# power_cpu.net
KiCad netlist of a schematic drawn in Altium Designer
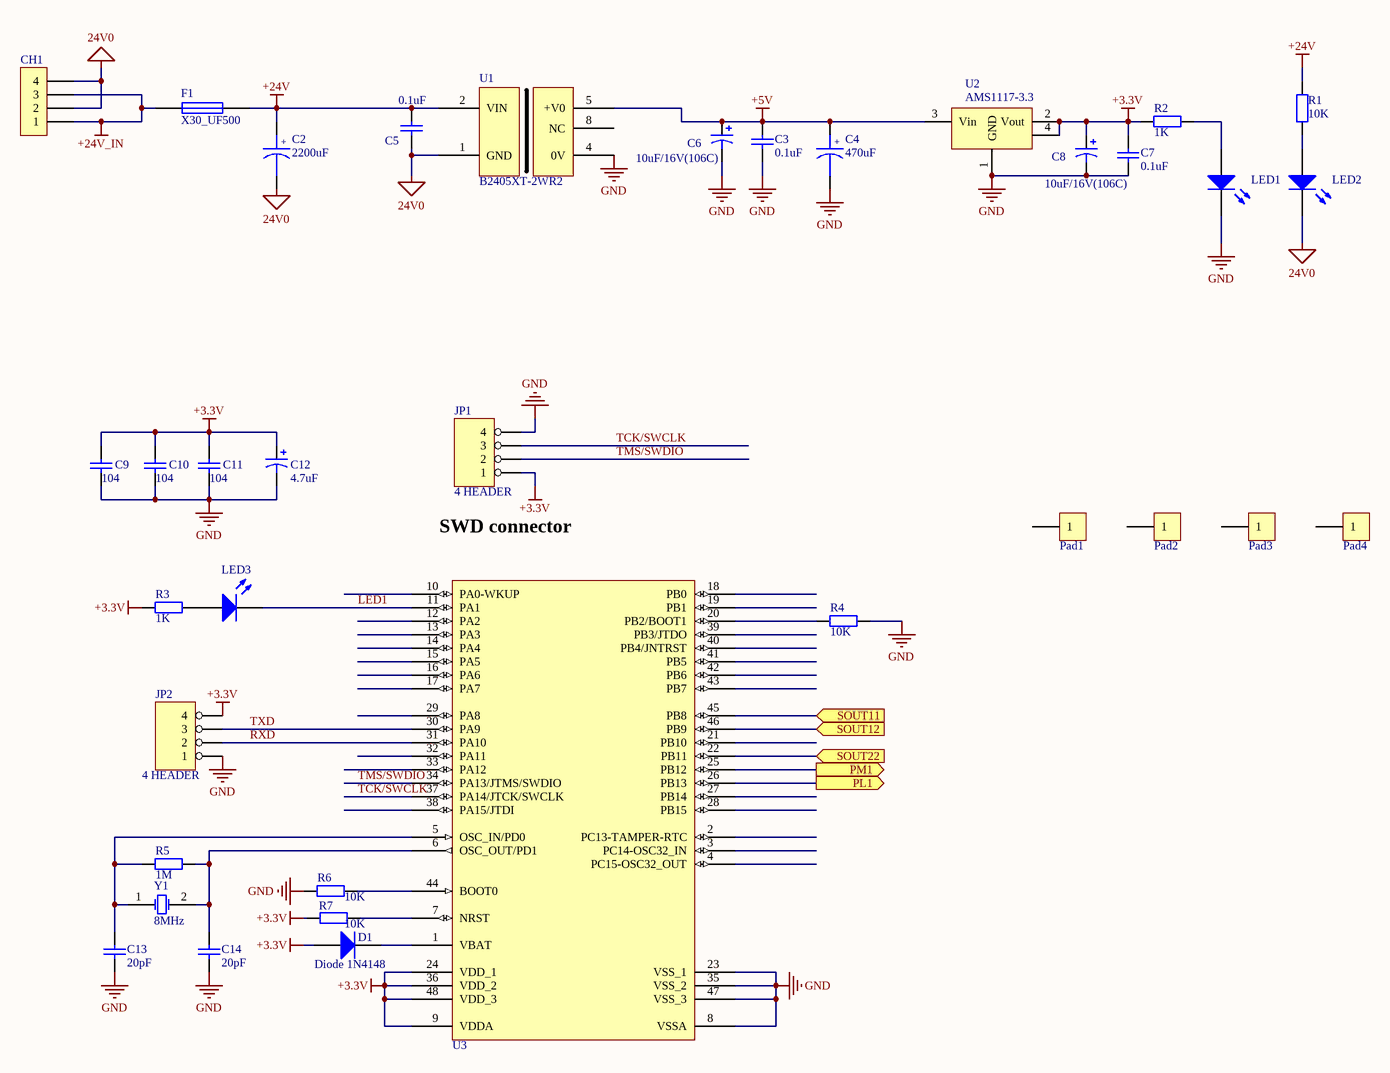
[diagram p0: power_cpu.SchDoc]

(export (version "E")
  (design (tool "Eeschema 10.0.6"))
  (components
    (comp (ref "C2")
      (value "C_2200uF")
      (footprint "C7.8*17")
      (fields (field (name "ALTIUM_UNNAMED_1") "2200uF"))
      (libsource (lib "myIntegrated_Library1") (part "C_2200uF"))
    )
    (comp (ref "C3")
      (value "0.1uF")
      (footprint "0805")
      (description "Capacitor")
      (fields (field (name "Comment") "Cap") (field (name "PUBLISHER") "Altium Limited"))
      (libsource (lib "Miscellaneous Devices") (part "Cap"))
    )
    (comp (ref "C4")
      (value "C_2200uF")
      (footprint "C5*10")
      (fields (field (name "ALTIUM_UNNAMED_1") "470uF"))
      (libsource (lib "myIntegrated_Library1") (part "C_2200uF"))
    )
    (comp (ref "C5")
      (value "0.1uF")
      (footprint "0805")
      (description "Capacitor")
      (fields (field (name "Comment") "Cap") (field (name "PUBLISHER") "Altium Limited"))
      (libsource (lib "Miscellaneous Devices") (part "Cap"))
    )
    (comp (ref "C6")
      (value "10uF/16V(106C)")
      (footprint "CAP A-3216")
      (description "Polarized Capacitor (Surface Mount)")
      (fields (field (name "Comment") "Cap Pol3") (field (name "PUBLISHER") "Altium Limited"))
      (libsource (lib "Miscellaneous Devices") (part "Cap Pol3"))
    )
    (comp (ref "C7")
      (value "0.1uF")
      (footprint "0805")
      (description "Capacitor")
      (fields (field (name "Comment") "Cap") (field (name "PUBLISHER") "Altium Limited"))
      (libsource (lib "Miscellaneous Devices") (part "Cap"))
    )
    (comp (ref "C8")
      (value "10uF/16V(106C)")
      (footprint "CAP A-3216")
      (description "Polarized Capacitor (Surface Mount)")
      (fields (field (name "Comment") "Cap Pol3") (field (name "PUBLISHER") "Altium Limited"))
      (libsource (lib "Miscellaneous Devices") (part "Cap Pol3"))
    )
    (comp (ref "C9")
      (value "104")
      (footprint "0805")
      (description "Capacitor")
      (fields (field (name "Comment") "Cap") (field (name "PUBLISHER") "Altium Limited"))
      (libsource (lib "Miscellaneous Devices") (part "Cap"))
    )
    (comp (ref "C10")
      (value "104")
      (footprint "0805")
      (description "Capacitor")
      (fields (field (name "Comment") "Cap") (field (name "PUBLISHER") "Altium Limited"))
      (libsource (lib "Miscellaneous Devices") (part "Cap"))
    )
    (comp (ref "C11")
      (value "104")
      (footprint "0805")
      (description "Capacitor")
      (fields (field (name "Comment") "Cap") (field (name "PUBLISHER") "Altium Limited"))
      (libsource (lib "Miscellaneous Devices") (part "Cap"))
    )
    (comp (ref "C12")
      (value "4.7uF")
      (footprint "3225[1210]")
      (description "Polarized Capacitor (Radial)")
      (fields (field (name "Comment") "Cap Pol1") (field (name "PUBLISHER") "Altium Limited"))
      (libsource (lib "Miscellaneous Devices") (part "Cap Pol1"))
    )
    (comp (ref "C13")
      (value "20pF")
      (footprint "0805")
      (description "Capacitor")
      (fields (field (name "Comment") "Cap") (field (name "PUBLISHER") "Altium Limited"))
      (libsource (lib "开发板元件库") (part "Cap"))
    )
    (comp (ref "C14")
      (value "20pF")
      (footprint "0805")
      (description "Capacitor")
      (fields (field (name "Comment") "Cap") (field (name "PUBLISHER") "Altium Limited"))
      (libsource (lib "开发板元件库") (part "Cap"))
    )
    (comp (ref "CH1")
      (value "HEADER1X4")
      (footprint "CH3.96-4PIN")
      (libsource (lib "myIntegrated_Library1") (part "HEADER1X4"))
    )
    (comp (ref "D1")
      (value "Diode 1N4148")
      (footprint "LL34")
      (description "High Conductance Fast Diode")
      (fields (field (name "PUBLISHER") "Altium Limited"))
      (libsource (lib "Miscellaneous Devices") (part "Diode 1N4148"))
    )
    (comp (ref "F1")
      (value "X30_UF500")
      (footprint "X30UF600")
      (description "Fuse")
      (fields (field (name "PUBLISHER") "Altium Limited"))
      (libsource (lib "Miscellaneous Devices") (part "Fuse 1"))
    )
    (comp (ref "JP1")
      (value "4 HEADER")
      (footprint "CON4_1.5")
      (description "4 Pin Header")
      (libsource (lib "Miscellaneous Devices") (part "4 HEADER"))
    )
    (comp (ref "JP2")
      (value "4 HEADER")
      (footprint "HDR1X4")
      (description "4 Pin Header")
      (libsource (lib "myIntegrated_Library1") (part "4 HEADER"))
    )
    (comp (ref "LED1")
      (value "~")
      (footprint "LED-0805")
      (description "Typical RED, GREEN, YELLOW, AMBER GaAs LED")
      (fields (field (name "PUBLISHER") "Altium Limited"))
      (libsource (lib "Miscellaneous Devices") (part "LED2"))
    )
    (comp (ref "LED2")
      (value "~")
      (footprint "LED-0805")
      (description "Typical RED, GREEN, YELLOW, AMBER GaAs LED")
      (fields (field (name "PUBLISHER") "Altium Limited"))
      (libsource (lib "Miscellaneous Devices") (part "LED2"))
    )
    (comp (ref "LED3")
      (value "~")
      (footprint "LED-0805")
      (description "Typical RED, GREEN, YELLOW, AMBER GaAs LED")
      (fields (field (name "PUBLISHER") "Altium Limited"))
      (libsource (lib "Miscellaneous Devices") (part "LED2"))
    )
    (comp (ref "Pad1")
      (value "Pad")
      (footprint "pad35")
      (libsource (lib "myIntegrated_Library1") (part "Pad"))
    )
    (comp (ref "Pad2")
      (value "Pad")
      (footprint "pad35")
      (libsource (lib "myIntegrated_Library1") (part "Pad"))
    )
    (comp (ref "Pad3")
      (value "Pad")
      (footprint "pad35")
      (libsource (lib "myIntegrated_Library1") (part "Pad"))
    )
    (comp (ref "Pad4")
      (value "Pad")
      (footprint "pad35")
      (libsource (lib "myIntegrated_Library1") (part "Pad"))
    )
    (comp (ref "R1")
      (value "10K")
      (footprint "0805")
      (description "Resistor")
      (fields (field (name "Comment") "Res2") (field (name "PUBLISHER") "Altium Limited"))
      (libsource (lib "") (part "Res2_1"))
    )
    (comp (ref "R2")
      (value "1K")
      (footprint "0805")
      (description "Resistor")
      (fields (field (name "Comment") "Res2") (field (name "PUBLISHER") "Altium Limited"))
      (libsource (lib "Miscellaneous Devices") (part "Res2"))
    )
    (comp (ref "R3")
      (value "1K")
      (footprint "0805")
      (description "Resistor")
      (fields (field (name "Comment") "Res2") (field (name "PUBLISHER") "Altium Limited"))
      (libsource (lib "Miscellaneous Devices") (part "Res2"))
    )
    (comp (ref "R4")
      (value "10K")
      (footprint "0805")
      (description "Resistor")
      (fields (field (name "Comment") "Res2") (field (name "PUBLISHER") "Altium Limited"))
      (libsource (lib "开发板元件库") (part "Res2"))
    )
    (comp (ref "R5")
      (value "1M")
      (footprint "0805")
      (description "Resistor")
      (fields (field (name "Comment") "Res2") (field (name "PUBLISHER") "Altium Limited"))
      (libsource (lib "开发板元件库") (part "Res2"))
    )
    (comp (ref "R6")
      (value "10K")
      (footprint "0805")
      (description "Resistor")
      (fields (field (name "Comment") "Res2") (field (name "PUBLISHER") "Altium Limited"))
      (libsource (lib "开发板元件库") (part "Res2"))
    )
    (comp (ref "R7")
      (value "10K")
      (footprint "0805")
      (description "Resistor")
      (fields (field (name "Comment") "Res2") (field (name "PUBLISHER") "Altium Limited"))
      (libsource (lib "开发板元件库") (part "Res2"))
    )
    (comp (ref "U1")
      (value "B2405XT-2WR2")
      (footprint "B2405XT-2WR2")
      (libsource (lib "myIntegrated_Library1") (part "B2405XT-2WR2"))
    )
    (comp (ref "U2")
      (value "AMS1117-3.3")
      (footprint "SOT223")
      (libsource (lib "货架电子标签元件库") (part "AMS1117-5"))
    )
    (comp (ref "U3")
      (value "STM32F103C8T6")
      (footprint "LQFP48")
      (libsource (lib "myIntegrated_Library1") (part "STM32F103C8T6"))
    )
    (comp (ref "Y1")
      (value "8MHz")
      (footprint "XTAL_US")
      (description "Crystal Oscillator")
      (fields (field (name "PUBLISHER") "Altium Limited"))
      (libsource (lib "战舰STM32开发板底板封装库") (part "XTAL"))
    )
  )
  (nets
    (net (code "1") (name "+3.3V") (class "Default")
      (node (ref "C10") (pin "2") (pinfunction "2_2") (pintype "passive"))
      (node (ref "C11") (pin "2") (pinfunction "2_2") (pintype "passive"))
      (node (ref "C12") (pin "1") (pinfunction "1_1") (pintype "passive"))
      (node (ref "C7") (pin "2") (pinfunction "2_2") (pintype "passive"))
      (node (ref "C8") (pin "1") (pinfunction "1_1") (pintype "passive"))
      (node (ref "C9") (pin "2") (pinfunction "2_2") (pintype "passive"))
      (node (ref "D1") (pin "1") (pinfunction "A_1") (pintype "passive"))
      (node (ref "JP1") (pin "1") (pinfunction "1_1") (pintype "passive"))
      (node (ref "JP2") (pin "4") (pinfunction "4_4") (pintype "passive"))
      (node (ref "R2") (pin "2") (pinfunction "2_2") (pintype "passive"))
      (node (ref "R3") (pin "2") (pinfunction "2_2") (pintype "passive"))
      (node (ref "R7") (pin "1") (pinfunction "1_1") (pintype "passive"))
      (node (ref "U2") (pin "2") (pinfunction "Vout_2") (pintype "passive"))
      (node (ref "U2") (pin "4") (pintype "passive"))
      (node (ref "U3") (pin "24") (pinfunction "VDD_1_24") (pintype "power_in"))
      (node (ref "U3") (pin "36") (pinfunction "VDD_2_36") (pintype "power_in"))
      (node (ref "U3") (pin "48") (pinfunction "VDD_3_48") (pintype "power_in"))
      (node (ref "U3") (pin "9") (pinfunction "VDDA_9") (pintype "power_in"))
    )
    (net (code "2") (name "+5V") (class "Default")
      (node (ref "C3") (pin "2") (pinfunction "2_2") (pintype "passive"))
      (node (ref "C4") (pin "1") (pinfunction "1_1") (pintype "passive"))
      (node (ref "C6") (pin "1") (pinfunction "1_1") (pintype "passive"))
      (node (ref "U1") (pin "5") (pinfunction "+V0_5") (pintype "passive"))
      (node (ref "U2") (pin "3") (pinfunction "Vin_3") (pintype "passive"))
    )
    (net (code "3") (name "+24V") (class "Default")
      (node (ref "C2") (pin "1") (pinfunction "1_1") (pintype "passive"))
      (node (ref "C5") (pin "2") (pinfunction "2_2") (pintype "passive"))
      (node (ref "F1") (pin "2") (pinfunction "2_2") (pintype "passive"))
      (node (ref "R1") (pin "2") (pinfunction "2_2") (pintype "passive"))
      (node (ref "U1") (pin "2") (pinfunction "VIN_2") (pintype "passive"))
    )
    (net (code "4") (name "+24V_IN") (class "Default")
      (node (ref "CH1") (pin "1") (pinfunction "1_1") (pintype "passive"))
      (node (ref "CH1") (pin "3") (pinfunction "3_3") (pintype "passive"))
      (node (ref "F1") (pin "1") (pinfunction "1_1") (pintype "passive"))
    )
    (net (code "5") (name "/LED1") (class "Default")
      (node (ref "LED3") (pin "2") (pinfunction "K_2") (pintype "passive"))
      (node (ref "U3") (pin "11") (pinfunction "PA1_11") (pintype "bidirectional"))
    )
    (net (code "6") (name "/PL1") (class "Default")
      (node (ref "U3") (pin "26") (pinfunction "PB13_26") (pintype "bidirectional"))
    )
    (net (code "7") (name "/PM1") (class "Default")
      (node (ref "U3") (pin "25") (pinfunction "PB12_25") (pintype "bidirectional"))
    )
    (net (code "8") (name "/RXD") (class "Default")
      (node (ref "JP2") (pin "2") (pinfunction "2_2") (pintype "passive"))
      (node (ref "U3") (pin "31") (pinfunction "PA10_31") (pintype "bidirectional"))
    )
    (net (code "9") (name "/SOUT11") (class "Default")
      (node (ref "U3") (pin "45") (pinfunction "PB8_45") (pintype "bidirectional"))
    )
    (net (code "10") (name "/SOUT12") (class "Default")
      (node (ref "U3") (pin "46") (pinfunction "PB9_46") (pintype "bidirectional"))
    )
    (net (code "11") (name "/SOUT22") (class "Default")
      (node (ref "U3") (pin "22") (pinfunction "PB11_22") (pintype "bidirectional"))
    )
    (net (code "12") (name "/TCK{slash}SWCLK") (class "Default")
      (node (ref "JP1") (pin "3") (pinfunction "3_3") (pintype "passive"))
      (node (ref "U3") (pin "37") (pinfunction "PA14/JTCK/SWCLK_37") (pintype "bidirectional"))
    )
    (net (code "13") (name "/TMS{slash}SWDIO") (class "Default")
      (node (ref "JP1") (pin "2") (pinfunction "2_2") (pintype "passive"))
      (node (ref "U3") (pin "34") (pinfunction "PA13/JTMS/SWDIO_34") (pintype "bidirectional"))
    )
    (net (code "14") (name "/TXD") (class "Default")
      (node (ref "JP2") (pin "3") (pinfunction "3_3") (pintype "passive"))
      (node (ref "U3") (pin "30") (pinfunction "PA9_30") (pintype "bidirectional"))
    )
    (net (code "15") (name "24V0") (class "Default")
      (node (ref "C2") (pin "2") (pinfunction "2_2") (pintype "passive"))
      (node (ref "C5") (pin "1") (pinfunction "1_1") (pintype "passive"))
      (node (ref "CH1") (pin "2") (pinfunction "2_2") (pintype "passive"))
      (node (ref "CH1") (pin "4") (pinfunction "4_4") (pintype "passive"))
      (node (ref "LED2") (pin "2") (pinfunction "K_2") (pintype "passive"))
      (node (ref "U1") (pin "1") (pinfunction "GND_1") (pintype "passive"))
    )
    (net (code "16") (name "GND") (class "Default")
      (node (ref "C10") (pin "1") (pinfunction "1_1") (pintype "passive"))
      (node (ref "C11") (pin "1") (pinfunction "1_1") (pintype "passive"))
      (node (ref "C12") (pin "2") (pinfunction "2_2") (pintype "passive"))
      (node (ref "C13") (pin "1") (pinfunction "1_1") (pintype "passive"))
      (node (ref "C14") (pin "1") (pinfunction "1_1") (pintype "passive"))
      (node (ref "C3") (pin "1") (pinfunction "1_1") (pintype "passive"))
      (node (ref "C4") (pin "2") (pinfunction "2_2") (pintype "passive"))
      (node (ref "C6") (pin "2") (pinfunction "2_2") (pintype "passive"))
      (node (ref "C7") (pin "1") (pinfunction "1_1") (pintype "passive"))
      (node (ref "C8") (pin "2") (pinfunction "2_2") (pintype "passive"))
      (node (ref "C9") (pin "1") (pinfunction "1_1") (pintype "passive"))
      (node (ref "JP1") (pin "4") (pinfunction "4_4") (pintype "passive"))
      (node (ref "JP2") (pin "1") (pinfunction "1_1") (pintype "passive"))
      (node (ref "LED1") (pin "2") (pinfunction "K_2") (pintype "passive"))
      (node (ref "R4") (pin "2") (pinfunction "2_2") (pintype "passive"))
      (node (ref "R6") (pin "1") (pinfunction "1_1") (pintype "passive"))
      (node (ref "U1") (pin "4") (pinfunction "0V_4") (pintype "passive"))
      (node (ref "U2") (pin "1") (pinfunction "GND_1") (pintype "passive"))
      (node (ref "U3") (pin "23") (pinfunction "VSS_1_23") (pintype "power_in"))
      (node (ref "U3") (pin "35") (pinfunction "VSS_2_35") (pintype "power_in"))
      (node (ref "U3") (pin "47") (pinfunction "VSS_3_47") (pintype "power_in"))
      (node (ref "U3") (pin "8") (pinfunction "VSSA_8") (pintype "power_in"))
    )
    (net (code "17") (name "Net-(D1-K)") (class "Default")
      (node (ref "D1") (pin "2") (pinfunction "K_2") (pintype "passive"))
      (node (ref "U3") (pin "1") (pinfunction "VBAT_1") (pintype "power_in"))
    )
    (net (code "18") (name "Net-(LED1-A)") (class "Default")
      (node (ref "LED1") (pin "1") (pinfunction "A_1") (pintype "passive"))
      (node (ref "R2") (pin "1") (pinfunction "1_1") (pintype "passive"))
    )
    (net (code "19") (name "Net-(LED2-A)") (class "Default")
      (node (ref "LED2") (pin "1") (pinfunction "A_1") (pintype "passive"))
      (node (ref "R1") (pin "1") (pinfunction "1_1") (pintype "passive"))
    )
    (net (code "20") (name "Net-(LED3-A)") (class "Default")
      (node (ref "LED3") (pin "1") (pinfunction "A_1") (pintype "passive"))
      (node (ref "R3") (pin "1") (pinfunction "1_1") (pintype "passive"))
    )
    (net (code "21") (name "Net-(U3-BOOT0)") (class "Default")
      (node (ref "R6") (pin "2") (pinfunction "2_2") (pintype "passive"))
      (node (ref "U3") (pin "44") (pinfunction "BOOT0_44") (pintype "input"))
    )
    (net (code "22") (name "Net-(U3-NRST)") (class "Default")
      (node (ref "R7") (pin "2") (pinfunction "2_2") (pintype "passive"))
      (node (ref "U3") (pin "7") (pinfunction "NRST_7") (pintype "bidirectional"))
    )
    (net (code "23") (name "Net-(U3-OSC_IN{slash}PD0)") (class "Default")
      (node (ref "C13") (pin "2") (pinfunction "2_2") (pintype "passive"))
      (node (ref "R5") (pin "1") (pinfunction "1_1") (pintype "passive"))
      (node (ref "U3") (pin "5") (pinfunction "OSC_IN/PD0_5") (pintype "input"))
      (node (ref "Y1") (pin "1") (pinfunction "OSC1_1") (pintype "passive"))
    )
    (net (code "24") (name "Net-(U3-OSC_OUT{slash}PD1)") (class "Default")
      (node (ref "C14") (pin "2") (pinfunction "2_2") (pintype "passive"))
      (node (ref "R5") (pin "2") (pinfunction "2_2") (pintype "passive"))
      (node (ref "U3") (pin "6") (pinfunction "OSC_OUT/PD1_6") (pintype "output"))
      (node (ref "Y1") (pin "2") (pinfunction "OSC2_2") (pintype "passive"))
    )
    (net (code "25") (name "Net-(U3-PB2{slash}BOOT1)") (class "Default")
      (node (ref "R4") (pin "1") (pinfunction "1_1") (pintype "passive"))
      (node (ref "U3") (pin "20") (pinfunction "PB2/BOOT1_20") (pintype "bidirectional"))
    )
    (net (code "26") (name "unconnected-(Pad1-Pad1)") (class "Default")
      (node (ref "Pad1") (pin "1") (pinfunction "1_1") (pintype "passive"))
    )
    (net (code "27") (name "unconnected-(Pad2-Pad1)") (class "Default")
      (node (ref "Pad2") (pin "1") (pinfunction "1_1") (pintype "passive"))
    )
    (net (code "28") (name "unconnected-(Pad3-Pad1)") (class "Default")
      (node (ref "Pad3") (pin "1") (pinfunction "1_1") (pintype "passive"))
    )
    (net (code "29") (name "unconnected-(Pad4-Pad1)") (class "Default")
      (node (ref "Pad4") (pin "1") (pinfunction "1_1") (pintype "passive"))
    )
    (net (code "30") (name "unconnected-(U1-NC-Pad8)") (class "Default")
      (node (ref "U1") (pin "8") (pinfunction "NC_8") (pintype "passive"))
    )
    (net (code "31") (name "unconnected-(U3-PA0-WKUP-Pad10)") (class "Default")
      (node (ref "U3") (pin "10") (pinfunction "PA0-WKUP_10") (pintype "bidirectional"))
    )
    (net (code "32") (name "unconnected-(U3-PA2-Pad12)") (class "Default")
      (node (ref "U3") (pin "12") (pinfunction "PA2_12") (pintype "bidirectional"))
    )
    (net (code "33") (name "unconnected-(U3-PA3-Pad13)") (class "Default")
      (node (ref "U3") (pin "13") (pinfunction "PA3_13") (pintype "bidirectional"))
    )
    (net (code "34") (name "unconnected-(U3-PA4-Pad14)") (class "Default")
      (node (ref "U3") (pin "14") (pinfunction "PA4_14") (pintype "bidirectional"))
    )
    (net (code "35") (name "unconnected-(U3-PA5-Pad15)") (class "Default")
      (node (ref "U3") (pin "15") (pinfunction "PA5_15") (pintype "bidirectional"))
    )
    (net (code "36") (name "unconnected-(U3-PA6-Pad16)") (class "Default")
      (node (ref "U3") (pin "16") (pinfunction "PA6_16") (pintype "bidirectional"))
    )
    (net (code "37") (name "unconnected-(U3-PA7-Pad17)") (class "Default")
      (node (ref "U3") (pin "17") (pinfunction "PA7_17") (pintype "bidirectional"))
    )
    (net (code "38") (name "unconnected-(U3-PA8-Pad29)") (class "Default")
      (node (ref "U3") (pin "29") (pinfunction "PA8_29") (pintype "bidirectional"))
    )
    (net (code "39") (name "unconnected-(U3-PA11-Pad32)") (class "Default")
      (node (ref "U3") (pin "32") (pinfunction "PA11_32") (pintype "bidirectional"))
    )
    (net (code "40") (name "unconnected-(U3-PA12-Pad33)") (class "Default")
      (node (ref "U3") (pin "33") (pinfunction "PA12_33") (pintype "bidirectional"))
    )
    (net (code "41") (name "unconnected-(U3-PA15{slash}JTDI-Pad38)") (class "Default")
      (node (ref "U3") (pin "38") (pinfunction "PA15/JTDI_38") (pintype "bidirectional"))
    )
    (net (code "42") (name "unconnected-(U3-PB0-Pad18)") (class "Default")
      (node (ref "U3") (pin "18") (pinfunction "PB0_18") (pintype "bidirectional"))
    )
    (net (code "43") (name "unconnected-(U3-PB1-Pad19)") (class "Default")
      (node (ref "U3") (pin "19") (pinfunction "PB1_19") (pintype "bidirectional"))
    )
    (net (code "44") (name "unconnected-(U3-PB3{slash}JTDO-Pad39)") (class "Default")
      (node (ref "U3") (pin "39") (pinfunction "PB3/JTDO_39") (pintype "bidirectional"))
    )
    (net (code "45") (name "unconnected-(U3-PB4{slash}JNTRST-Pad40)") (class "Default")
      (node (ref "U3") (pin "40") (pinfunction "PB4/JNTRST_40") (pintype "bidirectional"))
    )
    (net (code "46") (name "unconnected-(U3-PB5-Pad41)") (class "Default")
      (node (ref "U3") (pin "41") (pinfunction "PB5_41") (pintype "bidirectional"))
    )
    (net (code "47") (name "unconnected-(U3-PB6-Pad42)") (class "Default")
      (node (ref "U3") (pin "42") (pinfunction "PB6_42") (pintype "bidirectional"))
    )
    (net (code "48") (name "unconnected-(U3-PB7-Pad43)") (class "Default")
      (node (ref "U3") (pin "43") (pinfunction "PB7_43") (pintype "bidirectional"))
    )
    (net (code "49") (name "unconnected-(U3-PB10-Pad21)") (class "Default")
      (node (ref "U3") (pin "21") (pinfunction "PB10_21") (pintype "bidirectional"))
    )
    (net (code "50") (name "unconnected-(U3-PB14-Pad27)") (class "Default")
      (node (ref "U3") (pin "27") (pinfunction "PB14_27") (pintype "bidirectional"))
    )
    (net (code "51") (name "unconnected-(U3-PB15-Pad28)") (class "Default")
      (node (ref "U3") (pin "28") (pinfunction "PB15_28") (pintype "bidirectional"))
    )
    (net (code "52") (name "unconnected-(U3-PC13-TAMPER-RTC-Pad2)") (class "Default")
      (node (ref "U3") (pin "2") (pinfunction "PC13-TAMPER-RTC_2") (pintype "bidirectional"))
    )
    (net (code "53") (name "unconnected-(U3-PC14-OSC32_IN-Pad3)") (class "Default")
      (node (ref "U3") (pin "3") (pinfunction "PC14-OSC32_IN_3") (pintype "bidirectional"))
    )
    (net (code "54") (name "unconnected-(U3-PC15-OSC32_OUT-Pad4)") (class "Default")
      (node (ref "U3") (pin "4") (pinfunction "PC15-OSC32_OUT_4") (pintype "bidirectional"))
    )
  )
)
